# TPS40304_DEMO.net
KiCad netlist of a schematic drawn in Altium Designer
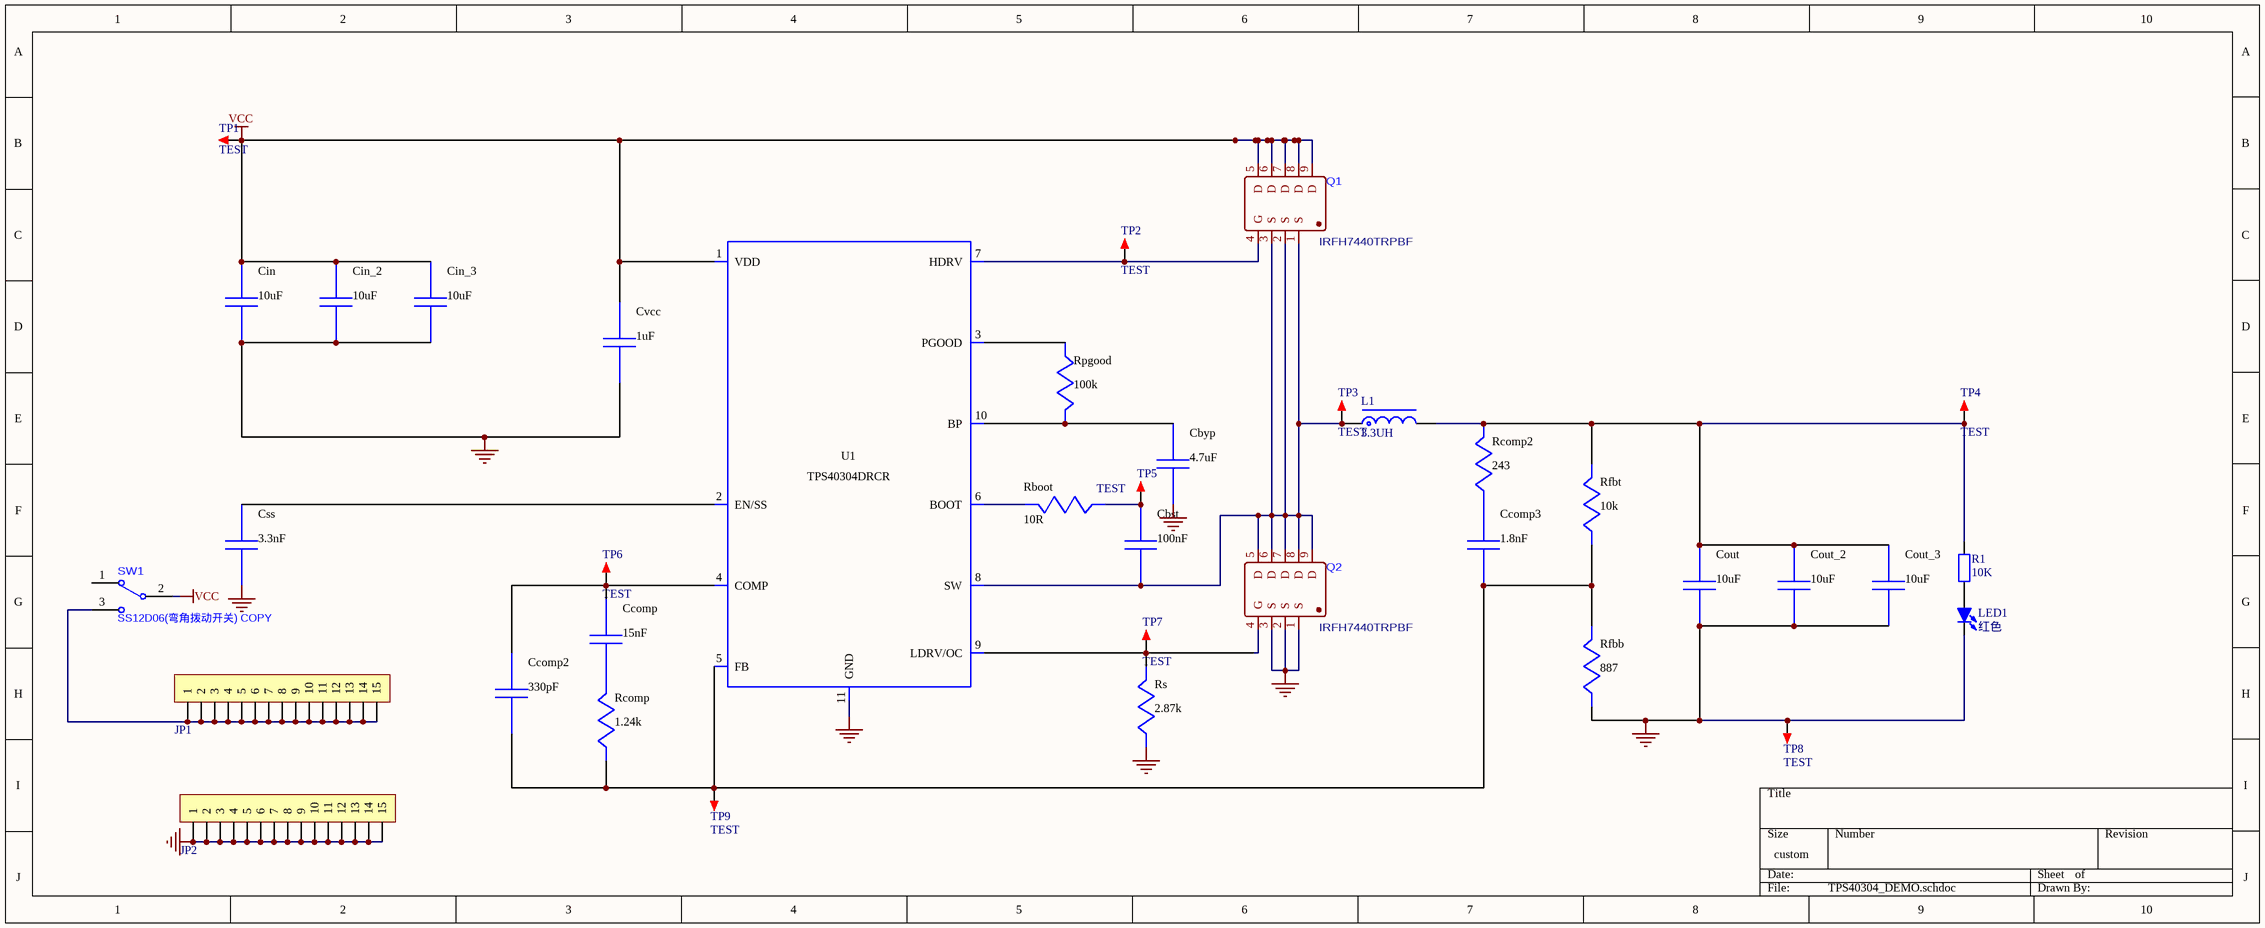
[diagram p0: TPS40304_DEMO.schdoc]

(export (version "E")
  (design (tool "Eeschema 10.0.6"))
  (components
    (comp (ref "Cbst")
      (value "100nF")
      (footprint "C 0805_L")
      (description "GRM155R71C104KA8")
      (fields (field (name "MANUFACTURER PART NUMBER") "GRM155R71C104KA88D"))
      (libsource (lib "TI WEBENCH") (part "Cbst"))
    )
    (comp (ref "Cbyp")
      (value "4.7uF")
      (footprint "C 0805_L")
      (description "LMK212BJ475KD-T")
      (libsource (lib "TI WEBENCH") (part "Cbyp"))
    )
    (comp (ref "Ccomp")
      (value "15nF")
      (footprint "C 0805_L")
      (description "CGA4F2C0G1H153J0")
      (fields (field (name "MANUFACTURER PART NUMBER") "CGA4F2C0G1H153J085AA"))
      (libsource (lib "TI WEBENCH") (part "Ccomp"))
    )
    (comp (ref "Ccomp2")
      (value "330pF")
      (footprint "C 0805_L")
      (description "CL21C331JBANNNC")
      (libsource (lib "TI WEBENCH") (part "Ccomp2"))
    )
    (comp (ref "Ccomp3")
      (value "1.8nF")
      (footprint "C 0805_L")
      (description "C2012C0G1H182K06")
      (fields (field (name "MANUFACTURER PART NUMBER") "C2012C0G1H182K060AA"))
      (libsource (lib "TI WEBENCH") (part "Ccomp3"))
    )
    (comp (ref "Cin")
      (value "10uF")
      (footprint "C 1210_L")
      (description "C3225X7R1H106M25")
      (fields (field (name "MANUFACTURER PART NUMBER") "C3225X7R1H106M250AC"))
      (libsource (lib "TI WEBENCH") (part "Cin"))
    )
    (comp (ref "Cin_2")
      (value "10uF")
      (footprint "C 1210_L")
      (description "C3225X7R1H106M25")
      (fields (field (name "MANUFACTURER PART NUMBER") "C3225X7R1H106M250AC"))
      (libsource (lib "TI WEBENCH") (part "Cin_2"))
    )
    (comp (ref "Cin_3")
      (value "10uF")
      (footprint "C 1206_L")
      (description "C3225X7R1H106M25")
      (fields (field (name "MANUFACTURER PART NUMBER") "C3225X7R1H106M250AC"))
      (libsource (lib "TI WEBENCH") (part "Cin_3"))
    )
    (comp (ref "Cout")
      (value "10uF")
      (footprint "C 1210_L")
      (description "CL32B106KBJNNWE")
      (libsource (lib "TI WEBENCH") (part "Cout"))
    )
    (comp (ref "Cout_2")
      (value "10uF")
      (footprint "C 1210_L")
      (description "CL32B106KBJNNWE")
      (libsource (lib "TI WEBENCH") (part "Cout_2"))
    )
    (comp (ref "Cout_3")
      (value "10uF")
      (footprint "C 1206_L")
      (description "CL32B106KBJNNWE")
      (libsource (lib "TI WEBENCH") (part "Cout_3"))
    )
    (comp (ref "Css")
      (value "3.3nF")
      (footprint "C 0805_L")
      (description "GRM033R71A332KA0")
      (fields (field (name "MANUFACTURER PART NUMBER") "GRM033R71A332KA01D"))
      (libsource (lib "TI WEBENCH") (part "Css"))
    )
    (comp (ref "Cvcc")
      (value "1uF")
      (footprint "C 0805_L")
      (description "TMK212B7105KG-T")
      (libsource (lib "TI WEBENCH") (part "Cvcc"))
    )
    (comp (ref "JP1")
      (value "HDR-1X15")
      (footprint "HDR2.54-LI-15P")
      (description "15P接插件")
      (fields (field (name "版权归属") "源创客"))
      (libsource (lib "4.6   - 接插件-脚距2.54") (part "Header 15"))
    )
    (comp (ref "JP2")
      (value "HDR-1X15")
      (footprint "HDR2.54-LI-15P")
      (description "15P接插件")
      (fields (field (name "版权归属") "源创客"))
      (libsource (lib "4.6   - 接插件-脚距2.54") (part "Header 15"))
    )
    (comp (ref "L1")
      (value "3.3UH")
      (footprint "SMD-L-1770")
      (description "贴片功率电感")
      (fields (field (name "版权归属") "源创客"))
      (libsource (lib "3.1   - 电阻-电容-电感") (part "L-CD"))
    )
    (comp (ref "LED1")
      (value "红色")
      (footprint "LED 0805G")
      (description "贴片LED")
      (fields (field (name "版权归属") "源创客"))
      (libsource (lib "9.1   - LED") (part "LED-SMD"))
    )
    (comp (ref "Q1")
      (value "IRFH7440TRPBF")
      (footprint "PQFN-8P_L5.8-W4.9-P1.27-LS6.0-BL")
      (libsource (lib "IRFH7440TRPBF") (part "IRFH7440TRPBF"))
    )
    (comp (ref "Q2")
      (value "IRFH7440TRPBF")
      (footprint "PQFN-8P_L5.8-W4.9-P1.27-LS6.0-BL")
      (libsource (lib "IRFH7440TRPBF") (part "IRFH7440TRPBF"))
    )
    (comp (ref "R1")
      (value "10K")
      (footprint "R 0805_L")
      (description "贴片电阻")
      (fields (field (name "版权归属") "源创客"))
      (libsource (lib "3.1   - 电阻-电容-电感") (part "R"))
    )
    (comp (ref "Rboot")
      (value "10R")
      (footprint "R 0805_L")
      (description "CRCW04022K87FKED")
      (libsource (lib "TI WEBENCH") (part "Rs"))
    )
    (comp (ref "Rcomp")
      (value "1.24k")
      (footprint "R 0805_L")
      (description "CRCW04021K24FKED")
      (libsource (lib "TI WEBENCH") (part "Rcomp"))
    )
    (comp (ref "Rcomp2")
      (value "243")
      (footprint "R 0805_L")
      (description "CRCW0402243RFKED")
      (libsource (lib "TI WEBENCH") (part "Rcomp2"))
    )
    (comp (ref "Rfbb")
      (value "887")
      (footprint "R 0805_L")
      (description "CRCW0402887RFKED")
      (libsource (lib "TI WEBENCH") (part "Rfbb"))
    )
    (comp (ref "Rfbt")
      (value "10k")
      (footprint "R 0805_L")
      (description "RC0201FR-0710KL")
      (libsource (lib "TI WEBENCH") (part "Rfbt"))
    )
    (comp (ref "Rpgood")
      (value "100k")
      (footprint "R 0805_L")
      (description "CRCW0402100KFKED")
      (libsource (lib "TI WEBENCH") (part "Rpgood"))
    )
    (comp (ref "Rs")
      (value "2.87k")
      (footprint "R 0805_L")
      (description "CRCW04022K87FKED")
      (libsource (lib "TI WEBENCH") (part "Rs"))
    )
    (comp (ref "SW1")
      (value "SS12D06(弯角拨动开关) COPY")
      (footprint "SS12_d06")
      (libsource (lib "SS12D06(弯角拨动开关)") (part "SS12D06(弯角拨动开关) COPY"))
    )
    (comp (ref "TP1")
      (value "TEST")
      (footprint "TEST 1.6")
      (description "测试点")
      (fields (field (name "版权归属") "源创客"))
      (libsource (lib "15.1 - 未分类器件") (part "TEST"))
    )
    (comp (ref "TP2")
      (value "TEST")
      (footprint "TEST 1.6")
      (description "测试点")
      (fields (field (name "版权归属") "源创客"))
      (libsource (lib "15.1 - 未分类器件") (part "TEST"))
    )
    (comp (ref "TP3")
      (value "TEST")
      (footprint "TEST 1.6")
      (description "测试点")
      (fields (field (name "版权归属") "源创客"))
      (libsource (lib "15.1 - 未分类器件") (part "TEST"))
    )
    (comp (ref "TP4")
      (value "TEST")
      (footprint "TEST 1.6")
      (description "测试点")
      (fields (field (name "版权归属") "源创客"))
      (libsource (lib "15.1 - 未分类器件") (part "TEST"))
    )
    (comp (ref "TP5")
      (value "TEST")
      (footprint "TEST 1.6")
      (description "测试点")
      (fields (field (name "版权归属") "源创客"))
      (libsource (lib "15.1 - 未分类器件") (part "TEST"))
    )
    (comp (ref "TP6")
      (value "TEST")
      (footprint "TEST 1.6")
      (description "测试点")
      (fields (field (name "版权归属") "源创客"))
      (libsource (lib "15.1 - 未分类器件") (part "TEST"))
    )
    (comp (ref "TP7")
      (value "TEST")
      (footprint "TEST 1.6")
      (description "测试点")
      (fields (field (name "版权归属") "源创客"))
      (libsource (lib "15.1 - 未分类器件") (part "TEST"))
    )
    (comp (ref "TP8")
      (value "TEST")
      (footprint "TEST 1.6")
      (description "测试点")
      (fields (field (name "版权归属") "源创客"))
      (libsource (lib "15.1 - 未分类器件") (part "TEST"))
    )
    (comp (ref "TP9")
      (value "TEST")
      (footprint "TEST 1.6")
      (description "测试点")
      (fields (field (name "版权归属") "源创客"))
      (libsource (lib "15.1 - 未分类器件") (part "TEST"))
    )
    (comp (ref "U1")
      (value "TPS40304DRCR")
      (footprint "WSON-10_L3.0-W3.0-P0.50-TL-EP")
      (fields (field (name "PACKAGEREFERENCE") "TPS40304DRCR"))
      (libsource (lib "TI WEBENCH") (part "U1"))
    )
  )
  (nets
    (net (code "1") (name "0") (class "Default")
      (node (ref "Cbyp") (pin "2") (pinfunction "2_2") (pintype "passive"))
      (node (ref "Cin") (pin "2") (pinfunction "2_2") (pintype "passive"))
      (node (ref "Cin_2") (pin "2") (pinfunction "2_2") (pintype "passive"))
      (node (ref "Cin_3") (pin "2") (pinfunction "2_2") (pintype "passive"))
      (node (ref "Cout") (pin "2") (pinfunction "2_2") (pintype "passive"))
      (node (ref "Cout_2") (pin "2") (pinfunction "2_2") (pintype "passive"))
      (node (ref "Cout_3") (pin "2") (pinfunction "2_2") (pintype "passive"))
      (node (ref "Css") (pin "2") (pinfunction "2_2") (pintype "passive"))
      (node (ref "Cvcc") (pin "2") (pinfunction "2_2") (pintype "passive"))
      (node (ref "JP2") (pin "1") (pinfunction "1_1") (pintype "passive"))
      (node (ref "JP2") (pin "10") (pinfunction "10_10") (pintype "passive"))
      (node (ref "JP2") (pin "11") (pinfunction "11_11") (pintype "passive"))
      (node (ref "JP2") (pin "12") (pinfunction "12_12") (pintype "passive"))
      (node (ref "JP2") (pin "13") (pinfunction "13_13") (pintype "passive"))
      (node (ref "JP2") (pin "14") (pinfunction "14_14") (pintype "passive"))
      (node (ref "JP2") (pin "15") (pinfunction "15_15") (pintype "passive"))
      (node (ref "JP2") (pin "2") (pinfunction "2_2") (pintype "passive"))
      (node (ref "JP2") (pin "3") (pinfunction "3_3") (pintype "passive"))
      (node (ref "JP2") (pin "4") (pinfunction "4_4") (pintype "passive"))
      (node (ref "JP2") (pin "5") (pinfunction "5_5") (pintype "passive"))
      (node (ref "JP2") (pin "6") (pinfunction "6_6") (pintype "passive"))
      (node (ref "JP2") (pin "7") (pinfunction "7_7") (pintype "passive"))
      (node (ref "JP2") (pin "8") (pinfunction "8_8") (pintype "passive"))
      (node (ref "JP2") (pin "9") (pinfunction "9_9") (pintype "passive"))
      (node (ref "LED1") (pin "2") (pinfunction "K_2") (pintype "passive"))
      (node (ref "Q2") (pin "1") (pinfunction "S_1") (pintype "passive"))
      (node (ref "Q2") (pin "2") (pinfunction "S_2") (pintype "passive"))
      (node (ref "Q2") (pin "3") (pinfunction "S_3") (pintype "passive"))
      (node (ref "Rfbb") (pin "2") (pinfunction "2_2") (pintype "passive"))
      (node (ref "Rs") (pin "2") (pinfunction "2_2") (pintype "passive"))
      (node (ref "TP8") (pin "1") (pinfunction "1_1") (pintype "passive"))
      (node (ref "U1") (pin "11") (pinfunction "GND_11") (pintype "passive"))
    )
    (net (code "2") (name "Net-(Cbst-Pad1)") (class "Default")
      (node (ref "Cbst") (pin "1") (pinfunction "1_1") (pintype "passive"))
      (node (ref "Rboot") (pin "2") (pinfunction "2_2") (pintype "passive"))
      (node (ref "TP5") (pin "1") (pinfunction "1_1") (pintype "passive"))
    )
    (net (code "3") (name "Net-(Ccomp-Pad1)") (class "Default")
      (node (ref "Ccomp") (pin "1") (pinfunction "1_1") (pintype "passive"))
      (node (ref "Rcomp") (pin "1") (pinfunction "1_1") (pintype "passive"))
    )
    (net (code "4") (name "Net-(Ccomp3-Pad1)") (class "Default")
      (node (ref "Ccomp3") (pin "1") (pinfunction "1_1") (pintype "passive"))
      (node (ref "Rcomp2") (pin "2") (pinfunction "2_2") (pintype "passive"))
    )
    (net (code "5") (name "Net-(Cout-Pad1)") (class "Default")
      (node (ref "Cout") (pin "1") (pinfunction "1_1") (pintype "passive"))
      (node (ref "Cout_2") (pin "1") (pinfunction "1_1") (pintype "passive"))
      (node (ref "Cout_3") (pin "1") (pinfunction "1_1") (pintype "passive"))
      (node (ref "L1") (pin "2") (pinfunction "2_2") (pintype "passive"))
      (node (ref "R1") (pin "1") (pinfunction "1_1") (pintype "passive"))
      (node (ref "Rcomp2") (pin "1") (pinfunction "1_1") (pintype "passive"))
      (node (ref "Rfbt") (pin "1") (pinfunction "1_1") (pintype "passive"))
      (node (ref "TP4") (pin "1") (pinfunction "1_1") (pintype "passive"))
    )
    (net (code "6") (name "Net-(JP1-Pad1)") (class "Default")
      (node (ref "JP1") (pin "1") (pinfunction "1_1") (pintype "passive"))
      (node (ref "JP1") (pin "10") (pinfunction "10_10") (pintype "passive"))
      (node (ref "JP1") (pin "11") (pinfunction "11_11") (pintype "passive"))
      (node (ref "JP1") (pin "12") (pinfunction "12_12") (pintype "passive"))
      (node (ref "JP1") (pin "13") (pinfunction "13_13") (pintype "passive"))
      (node (ref "JP1") (pin "14") (pinfunction "14_14") (pintype "passive"))
      (node (ref "JP1") (pin "15") (pinfunction "15_15") (pintype "passive"))
      (node (ref "JP1") (pin "2") (pinfunction "2_2") (pintype "passive"))
      (node (ref "JP1") (pin "3") (pinfunction "3_3") (pintype "passive"))
      (node (ref "JP1") (pin "4") (pinfunction "4_4") (pintype "passive"))
      (node (ref "JP1") (pin "5") (pinfunction "5_5") (pintype "passive"))
      (node (ref "JP1") (pin "6") (pinfunction "6_6") (pintype "passive"))
      (node (ref "JP1") (pin "7") (pinfunction "7_7") (pintype "passive"))
      (node (ref "JP1") (pin "8") (pinfunction "8_8") (pintype "passive"))
      (node (ref "JP1") (pin "9") (pinfunction "9_9") (pintype "passive"))
      (node (ref "SW1") (pin "3") (pinfunction "3_3") (pintype "passive"))
    )
    (net (code "7") (name "Net-(LED1-A)") (class "Default")
      (node (ref "LED1") (pin "1") (pinfunction "A_1") (pintype "passive"))
      (node (ref "R1") (pin "2") (pinfunction "2_2") (pintype "passive"))
    )
    (net (code "8") (name "Net-(Q1-G)") (class "Default")
      (node (ref "Q1") (pin "4") (pinfunction "G_4") (pintype "passive"))
      (node (ref "TP2") (pin "1") (pinfunction "1_1") (pintype "passive"))
      (node (ref "U1") (pin "7") (pinfunction "HDRV_7") (pintype "passive"))
    )
    (net (code "9") (name "Net-(Q2-G)") (class "Default")
      (node (ref "Q2") (pin "4") (pinfunction "G_4") (pintype "passive"))
      (node (ref "Rs") (pin "1") (pinfunction "1_1") (pintype "passive"))
      (node (ref "TP7") (pin "1") (pinfunction "1_1") (pintype "passive"))
      (node (ref "U1") (pin "9") (pinfunction "LDRV/OC_9") (pintype "passive"))
    )
    (net (code "10") (name "Net-(U1-BOOT)") (class "Default")
      (node (ref "Rboot") (pin "1") (pinfunction "1_1") (pintype "passive"))
      (node (ref "U1") (pin "6") (pinfunction "BOOT_6") (pintype "passive"))
    )
    (net (code "11") (name "Net-(U1-BP)") (class "Default")
      (node (ref "Cbyp") (pin "1") (pinfunction "1_1") (pintype "passive"))
      (node (ref "Rpgood") (pin "1") (pinfunction "1_1") (pintype "passive"))
      (node (ref "U1") (pin "10") (pinfunction "BP_10") (pintype "passive"))
    )
    (net (code "12") (name "Net-(U1-COMP)") (class "Default")
      (node (ref "Ccomp") (pin "2") (pinfunction "2_2") (pintype "passive"))
      (node (ref "Ccomp2") (pin "2") (pinfunction "2_2") (pintype "passive"))
      (node (ref "TP6") (pin "1") (pinfunction "1_1") (pintype "passive"))
      (node (ref "U1") (pin "4") (pinfunction "COMP_4") (pintype "passive"))
    )
    (net (code "13") (name "Net-(U1-EN{slash}SS)") (class "Default")
      (node (ref "Css") (pin "1") (pinfunction "1_1") (pintype "passive"))
      (node (ref "U1") (pin "2") (pinfunction "EN/SS_2") (pintype "passive"))
    )
    (net (code "14") (name "Net-(U1-FB)") (class "Default")
      (node (ref "Ccomp2") (pin "1") (pinfunction "1_1") (pintype "passive"))
      (node (ref "Ccomp3") (pin "2") (pinfunction "2_2") (pintype "passive"))
      (node (ref "Rcomp") (pin "2") (pinfunction "2_2") (pintype "passive"))
      (node (ref "Rfbb") (pin "1") (pinfunction "1_1") (pintype "passive"))
      (node (ref "Rfbt") (pin "2") (pinfunction "2_2") (pintype "passive"))
      (node (ref "TP9") (pin "1") (pinfunction "1_1") (pintype "passive"))
      (node (ref "U1") (pin "5") (pinfunction "FB_5") (pintype "passive"))
    )
    (net (code "15") (name "Net-(U1-PGOOD)") (class "Default")
      (node (ref "Rpgood") (pin "2") (pinfunction "2_2") (pintype "passive"))
      (node (ref "U1") (pin "3") (pinfunction "PGOOD_3") (pintype "passive"))
    )
    (net (code "16") (name "Net-(U1-SW)") (class "Default")
      (node (ref "Cbst") (pin "2") (pinfunction "2_2") (pintype "passive"))
      (node (ref "L1") (pin "1") (pinfunction "1_1") (pintype "passive"))
      (node (ref "Q1") (pin "1") (pinfunction "S_1") (pintype "passive"))
      (node (ref "Q1") (pin "2") (pinfunction "S_2") (pintype "passive"))
      (node (ref "Q1") (pin "3") (pinfunction "S_3") (pintype "passive"))
      (node (ref "Q2") (pin "5") (pinfunction "D_5") (pintype "passive"))
      (node (ref "Q2") (pin "6") (pinfunction "D_6") (pintype "passive"))
      (node (ref "Q2") (pin "7") (pinfunction "D_7") (pintype "passive"))
      (node (ref "Q2") (pin "8") (pinfunction "D_8") (pintype "passive"))
      (node (ref "Q2") (pin "9") (pinfunction "D_9") (pintype "passive"))
      (node (ref "TP3") (pin "1") (pinfunction "1_1") (pintype "passive"))
      (node (ref "U1") (pin "8") (pinfunction "SW_8") (pintype "passive"))
    )
    (net (code "17") (name "VCC") (class "Default")
      (node (ref "Cin") (pin "1") (pinfunction "1_1") (pintype "passive"))
      (node (ref "Cin_2") (pin "1") (pinfunction "1_1") (pintype "passive"))
      (node (ref "Cin_3") (pin "1") (pinfunction "1_1") (pintype "passive"))
      (node (ref "Cvcc") (pin "1") (pinfunction "1_1") (pintype "passive"))
      (node (ref "Q1") (pin "5") (pinfunction "D_5") (pintype "passive"))
      (node (ref "Q1") (pin "6") (pinfunction "D_6") (pintype "passive"))
      (node (ref "Q1") (pin "7") (pinfunction "D_7") (pintype "passive"))
      (node (ref "Q1") (pin "8") (pinfunction "D_8") (pintype "passive"))
      (node (ref "Q1") (pin "9") (pinfunction "D_9") (pintype "passive"))
      (node (ref "SW1") (pin "2") (pinfunction "2_2") (pintype "passive"))
      (node (ref "TP1") (pin "1") (pinfunction "1_1") (pintype "passive"))
      (node (ref "U1") (pin "1") (pinfunction "VDD_1") (pintype "passive"))
    )
    (net (code "18") (name "unconnected-(SW1-Pad1)") (class "Default")
      (node (ref "SW1") (pin "1") (pinfunction "1_1") (pintype "passive"))
    )
  )
)
